# sensordrampear.net
KiCad netlist of a schematic drawn in EAGLE
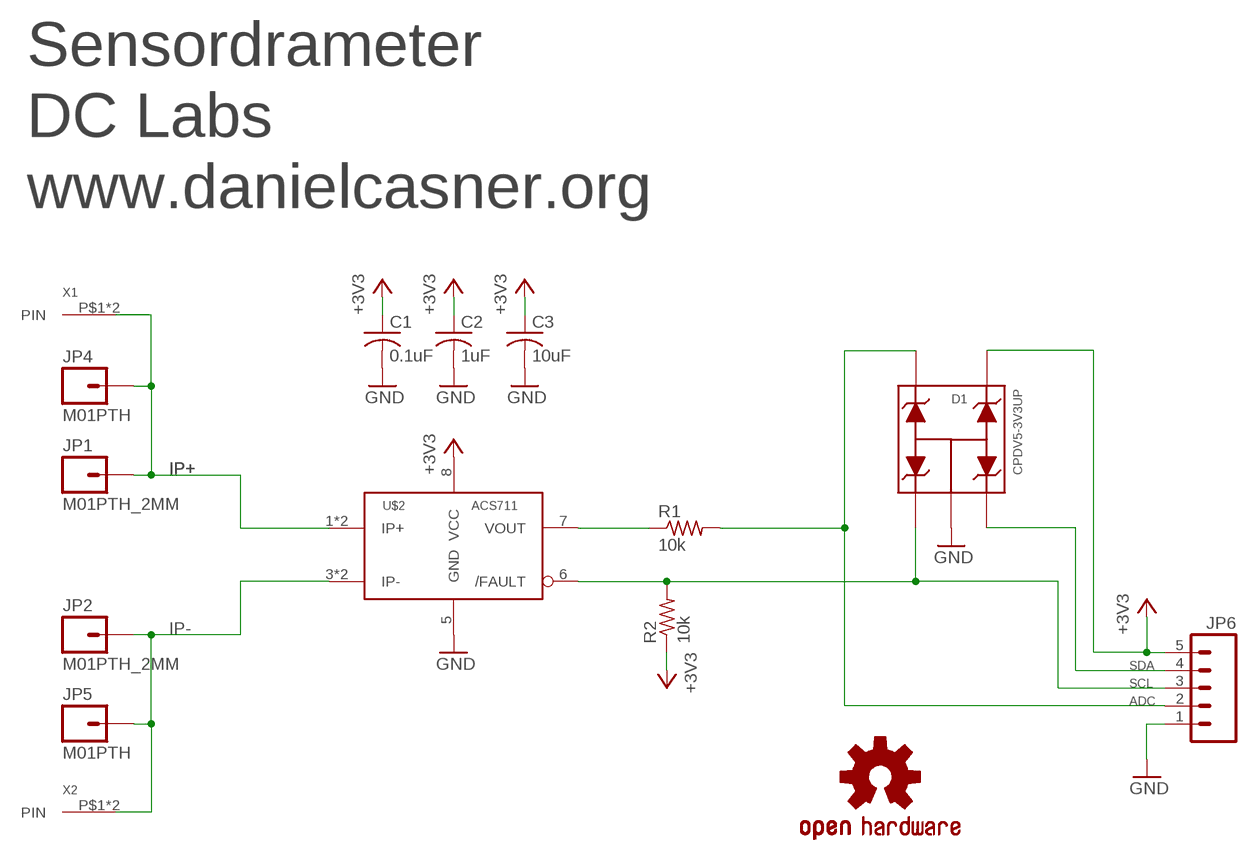
[diagram p0: schematic, sheet 1]

(export (version "E")
  (design (tool "Eeschema 10.0.6"))
  (components
    (comp (ref "C1")
      (value "0.1uF")
      (footprint "eagle-import:C0805")
      (libsource (lib "eagle-import") (part "C-USC0805"))
    )
    (comp (ref "C2")
      (value "1uF")
      (footprint "eagle-import:C0805")
      (libsource (lib "eagle-import") (part "C-USC0805"))
    )
    (comp (ref "C3")
      (value "10uF")
      (footprint "eagle-import:C0805")
      (libsource (lib "eagle-import") (part "C-USC0805"))
    )
    (comp (ref "D1")
      (value "CPDV5-3V3UP")
      (footprint "eagle-import:SOT353")
      (libsource (lib "eagle-import") (part "CPDV5"))
    )
    (comp (ref "JP1")
      (value "M01PTH_2MM")
      (footprint "eagle-import:1X01_2MM")
      (libsource (lib "eagle-import") (part "M01PTH_2MM"))
    )
    (comp (ref "JP2")
      (value "M01PTH_2MM")
      (footprint "eagle-import:1X01_2MM")
      (libsource (lib "eagle-import") (part "M01PTH_2MM"))
    )
    (comp (ref "JP4")
      (value "M01PTH")
      (footprint "eagle-import:1X01")
      (libsource (lib "eagle-import") (part "M01PTH"))
    )
    (comp (ref "JP5")
      (value "M01PTH")
      (footprint "eagle-import:1X01")
      (libsource (lib "eagle-import") (part "M01PTH"))
    )
    (comp (ref "JP6")
      (value "M05PTH_LONGPADS")
      (footprint "eagle-import:1X05_LONGPADS")
      (libsource (lib "eagle-import") (part "M05PTH_LONGPADS"))
    )
    (comp (ref "R1")
      (value "10k")
      (footprint "eagle-import:R0402")
      (libsource (lib "eagle-import") (part "R-US_R0402"))
    )
    (comp (ref "R2")
      (value "10k")
      (footprint "eagle-import:R0402")
      (libsource (lib "eagle-import") (part "R-US_R0402"))
    )
    (comp (ref "U$1")
      (value "OSHW-LOGOS")
      (footprint "eagle-import:OSHW-LOGO-S")
      (libsource (lib "eagle-import") (part "OSHW-LOGOS"))
    )
    (comp (ref "U$2")
      (value "ACS711")
      (footprint "eagle-import:SO8")
      (libsource (lib "eagle-import") (part "ACS711"))
    )
    (comp (ref "X1")
      (value "606X")
      (footprint "eagle-import:606X")
      (libsource (lib "eagle-import") (part "606X"))
    )
    (comp (ref "X2")
      (value "606X")
      (footprint "eagle-import:606X")
      (libsource (lib "eagle-import") (part "606X"))
    )
  )
  (nets
    (net (code "1") (name "+3V3") (class "Default")
      (node (ref "C1") (pin "1") (pinfunction "1_1") (pintype "passive"))
      (node (ref "C2") (pin "1") (pinfunction "1_1") (pintype "passive"))
      (node (ref "C3") (pin "1") (pinfunction "1_1") (pintype "passive"))
      (node (ref "D1") (pin "4") (pinfunction "P$4_4") (pintype "bidirectional"))
      (node (ref "JP6") (pin "5") (pinfunction "5_5") (pintype "passive"))
      (node (ref "R2") (pin "1") (pinfunction "1_1") (pintype "passive"))
      (node (ref "U$2") (pin "8") (pinfunction "VCC_8") (pintype "power_in"))
    )
    (net (code "2") (name "/ADC") (class "Default")
      (node (ref "D1") (pin "5") (pinfunction "P$5_5") (pintype "bidirectional"))
      (node (ref "JP6") (pin "2") (pinfunction "2_2") (pintype "passive"))
      (node (ref "R1") (pin "2") (pinfunction "2_2") (pintype "passive"))
    )
    (net (code "3") (name "/IP+") (class "Default")
      (node (ref "JP1") (pin "1") (pinfunction "1_1") (pintype "passive"))
      (node (ref "JP4") (pin "1") (pinfunction "1_1") (pintype "passive"))
      (node (ref "U$2") (pin "1") (pinfunction "IP+_1") (pintype "bidirectional"))
      (node (ref "U$2") (pin "2") (pinfunction "IP+_2") (pintype "bidirectional"))
      (node (ref "X1") (pin "P$1") (pinfunction "PIN_P$1") (pintype "bidirectional"))
      (node (ref "X1") (pin "P$2") (pinfunction "PIN_P$2") (pintype "bidirectional"))
    )
    (net (code "4") (name "/IP-") (class "Default")
      (node (ref "JP2") (pin "1") (pinfunction "1_1") (pintype "passive"))
      (node (ref "JP5") (pin "1") (pinfunction "1_1") (pintype "passive"))
      (node (ref "U$2") (pin "3") (pinfunction "IP-_3") (pintype "bidirectional"))
      (node (ref "U$2") (pin "4") (pinfunction "IP-_4") (pintype "bidirectional"))
      (node (ref "X2") (pin "P$1") (pinfunction "PIN_P$1") (pintype "bidirectional"))
      (node (ref "X2") (pin "P$2") (pinfunction "PIN_P$2") (pintype "bidirectional"))
    )
    (net (code "5") (name "/SCL") (class "Default")
      (node (ref "D1") (pin "1") (pinfunction "P$1_1") (pintype "bidirectional"))
      (node (ref "JP6") (pin "3") (pinfunction "3_3") (pintype "passive"))
      (node (ref "R2") (pin "2") (pinfunction "2_2") (pintype "passive"))
      (node (ref "U$2") (pin "6") (pinfunction "/FAULT_6") (pintype "bidirectional"))
    )
    (net (code "6") (name "/SDA") (class "Default")
      (node (ref "D1") (pin "3") (pinfunction "P$3_3") (pintype "bidirectional"))
      (node (ref "JP6") (pin "4") (pinfunction "4_4") (pintype "passive"))
    )
    (net (code "7") (name "GND") (class "Default")
      (node (ref "C1") (pin "2") (pinfunction "2_2") (pintype "passive"))
      (node (ref "C2") (pin "2") (pinfunction "2_2") (pintype "passive"))
      (node (ref "C3") (pin "2") (pinfunction "2_2") (pintype "passive"))
      (node (ref "D1") (pin "2") (pinfunction "P$2_2") (pintype "bidirectional"))
      (node (ref "JP6") (pin "1") (pinfunction "1_1") (pintype "passive"))
      (node (ref "U$2") (pin "5") (pinfunction "GND_5") (pintype "power_in"))
    )
    (net (code "8") (name "Net-(U$2-VOUT)") (class "Default")
      (node (ref "R1") (pin "1") (pinfunction "1_1") (pintype "passive"))
      (node (ref "U$2") (pin "7") (pinfunction "VOUT_7") (pintype "output"))
    )
  )
)
